# ver061_SignalAnalog.net
KiCad netlist of a schematic drawn in Altium Designer
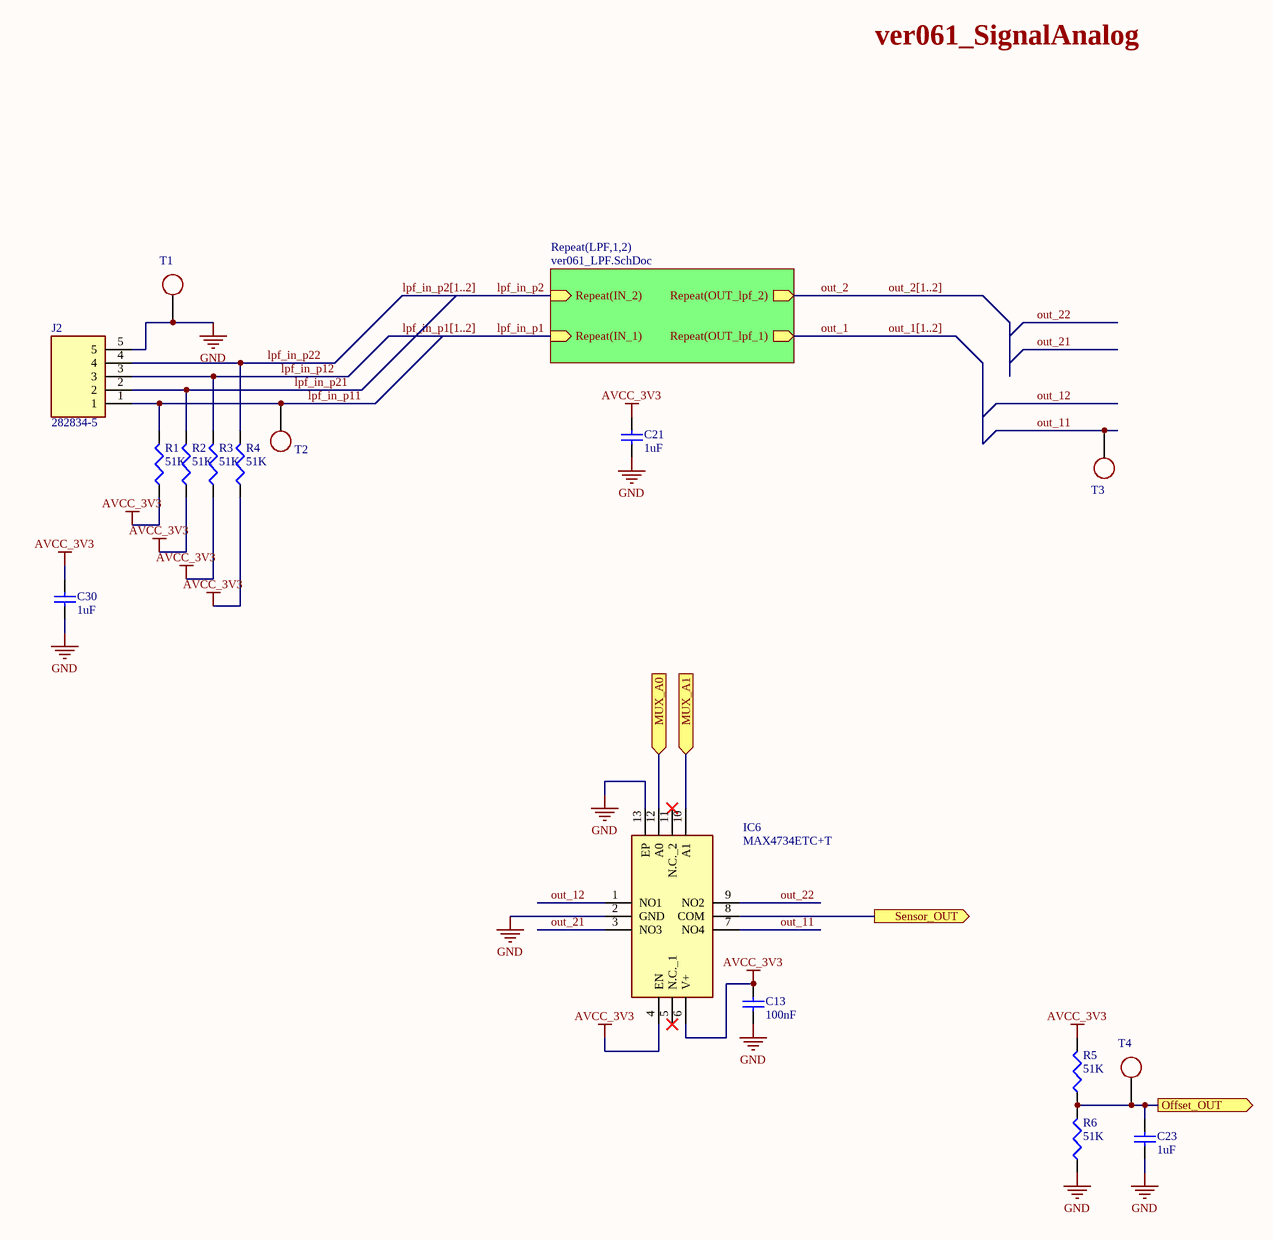
[diagram p0: ver061_SignalAnalog.SchDoc]

(export (version "E")
  (design (tool "Eeschema 10.0.6"))
  (components
    (comp (ref "C13")
      (value "100nF")
      (footprint "1608[0603]")
      (description "Capacitor (Semiconductor SIM Model)")
      (fields (field (name "Comment") "Cap Semi") (field (name "PUBLISHER") "Altium Limited"))
      (libsource (lib "Miscellaneous Devices") (part "Cap Semi"))
    )
    (comp (ref "C21")
      (value "1uF")
      (footprint "1608[0603]")
      (description "Capacitor (Semiconductor SIM Model)")
      (fields (field (name "Comment") "Cap Semi") (field (name "PUBLISHER") "Altium Limited"))
      (libsource (lib "Miscellaneous Devices") (part "Cap Semi"))
    )
    (comp (ref "C23")
      (value "1uF")
      (footprint "0402")
      (description "Capacitor (Semiconductor SIM Model)")
      (fields (field (name "Comment") "Cap Semi") (field (name "PUBLISHER") "Altium Limited"))
      (libsource (lib "Miscellaneous Devices") (part "Cap Semi"))
    )
    (comp (ref "C30")
      (value "1uF")
      (footprint "1608[0603]")
      (description "Capacitor (Semiconductor SIM Model)")
      (fields (field (name "Comment") "Cap Semi") (field (name "PUBLISHER") "Altium Limited"))
      (libsource (lib "Miscellaneous Devices") (part "Cap Semi"))
    )
    (comp (ref "IC6")
      (value "MAX4734ETC+T")
      (footprint "QFN50P300X300X80-13N")
      (description "Integrated Circuit")
      (fields (field (name "MOUSER PART NUMBER") "700-MAX4734ETCT"))
      (libsource (lib "*") (part "MAX4734ETC+T"))
    )
    (comp (ref "J2")
      (value "282834-5")
      (footprint "nanowire:2828345")
      (description "Connector")
      (fields (field (name "MOUSER PART NUMBER") "571-282834-5"))
      (libsource (lib "*") (part "282834-5"))
    )
    (comp (ref "R1")
      (value "51K")
      (footprint "RESC1608X55N")
      (description "Resistor")
      (fields (field (name "Comment") "Res3") (field (name "PUBLISHER") "Altium Limited"))
      (libsource (lib "Miscellaneous Devices") (part "Res3"))
    )
    (comp (ref "R2")
      (value "51K")
      (footprint "RESC1608X55N")
      (description "Resistor")
      (fields (field (name "Comment") "Res3") (field (name "PUBLISHER") "Altium Limited"))
      (libsource (lib "Miscellaneous Devices") (part "Res3"))
    )
    (comp (ref "R3")
      (value "51K")
      (footprint "RESC1608X55N")
      (description "Resistor")
      (fields (field (name "Comment") "Res3") (field (name "PUBLISHER") "Altium Limited"))
      (libsource (lib "Miscellaneous Devices") (part "Res3"))
    )
    (comp (ref "R4")
      (value "51K")
      (footprint "RESC1608X55N")
      (description "Resistor")
      (fields (field (name "Comment") "Res3") (field (name "PUBLISHER") "Altium Limited"))
      (libsource (lib "Miscellaneous Devices") (part "Res3"))
    )
    (comp (ref "R5")
      (value "51K")
      (footprint "RESC1005X35N")
      (description "Resistor")
      (fields (field (name "Comment") "Res3") (field (name "PUBLISHER") "Altium Limited"))
      (libsource (lib "Miscellaneous Devices") (part "Res3"))
    )
    (comp (ref "R6")
      (value "51K")
      (footprint "RESC1005X35N")
      (description "Resistor")
      (fields (field (name "Comment") "Res3") (field (name "PUBLISHER") "Altium Limited"))
      (libsource (lib "Miscellaneous Devices") (part "Res3"))
    )
    (comp (ref "T1")
      (value "TP_SMT")
      (footprint "TP_SMT_Round_0.6x0.6")
      (libsource (lib "nanowire") (part "TP_SMT"))
    )
    (comp (ref "T2")
      (value "TP_SMT")
      (footprint "TP_SMT_Round_0.6x0.6")
      (libsource (lib "nanowire") (part "TP_SMT"))
    )
    (comp (ref "T3")
      (value "TP_SMT")
      (footprint "TP_SMT_Round_0.6x0.6")
      (libsource (lib "nanowire") (part "TP_SMT"))
    )
    (comp (ref "T4")
      (value "TP_SMT")
      (footprint "TP_SMT_Round_0.6x0.6")
      (libsource (lib "nanowire") (part "TP_SMT"))
    )
  )
  (nets
    (net (code "1") (name "/MUX_A0") (class "Default")
      (node (ref "IC6") (pin "12") (pinfunction "A0_12") (pintype "passive"))
    )
    (net (code "2") (name "/MUX_A1") (class "Default")
      (node (ref "IC6") (pin "10") (pinfunction "A1_10") (pintype "passive"))
    )
    (net (code "3") (name "/Offset_OUT") (class "Default")
      (node (ref "C23") (pin "2") (pinfunction "2_2") (pintype "passive"))
      (node (ref "R5") (pin "1") (pinfunction "1_1") (pintype "passive"))
      (node (ref "R6") (pin "2") (pinfunction "2_2") (pintype "passive"))
      (node (ref "T4") (pin "1") (pinfunction "1_1") (pintype "passive"))
    )
    (net (code "4") (name "/Sensor_OUT") (class "Default")
      (node (ref "IC6") (pin "8") (pinfunction "COM_8") (pintype "passive"))
    )
    (net (code "9") (name "/lpf_in_p11") (class "Default")
      (node (ref "J2") (pin "1") (pinfunction "1_1") (pintype "passive"))
      (node (ref "R1") (pin "2") (pinfunction "2_2") (pintype "passive"))
      (node (ref "T2") (pin "1") (pinfunction "1_1") (pintype "passive"))
    )
    (net (code "10") (name "/lpf_in_p12") (class "Default")
      (node (ref "J2") (pin "3") (pinfunction "3_3") (pintype "passive"))
      (node (ref "R3") (pin "2") (pinfunction "2_2") (pintype "passive"))
    )
    (net (code "11") (name "/lpf_in_p21") (class "Default")
      (node (ref "J2") (pin "2") (pinfunction "2_2") (pintype "passive"))
      (node (ref "R2") (pin "2") (pinfunction "2_2") (pintype "passive"))
    )
    (net (code "12") (name "/lpf_in_p22") (class "Default")
      (node (ref "J2") (pin "4") (pinfunction "4_4") (pintype "passive"))
      (node (ref "R4") (pin "2") (pinfunction "2_2") (pintype "passive"))
    )
    (net (code "17") (name "/out_11") (class "Default")
      (node (ref "IC6") (pin "7") (pinfunction "NO4_7") (pintype "passive"))
      (node (ref "T3") (pin "1") (pinfunction "1_1") (pintype "passive"))
    )
    (net (code "18") (name "/out_12") (class "Default")
      (node (ref "IC6") (pin "1") (pinfunction "NO1_1") (pintype "passive"))
    )
    (net (code "19") (name "/out_21") (class "Default")
      (node (ref "IC6") (pin "3") (pinfunction "NO3_3") (pintype "passive"))
    )
    (net (code "20") (name "/out_22") (class "Default")
      (node (ref "IC6") (pin "9") (pinfunction "NO2_9") (pintype "passive"))
    )
    (net (code "21") (name "AVCC_3V3") (class "Default")
      (node (ref "C13") (pin "2") (pinfunction "2_2") (pintype "passive"))
      (node (ref "C21") (pin "2") (pinfunction "2_2") (pintype "passive"))
      (node (ref "C30") (pin "2") (pinfunction "2_2") (pintype "passive"))
      (node (ref "IC6") (pin "4") (pinfunction "EN_4") (pintype "passive"))
      (node (ref "IC6") (pin "6") (pinfunction "V+_6") (pintype "passive"))
      (node (ref "R1") (pin "1") (pinfunction "1_1") (pintype "passive"))
      (node (ref "R2") (pin "1") (pinfunction "1_1") (pintype "passive"))
      (node (ref "R3") (pin "1") (pinfunction "1_1") (pintype "passive"))
      (node (ref "R4") (pin "1") (pinfunction "1_1") (pintype "passive"))
      (node (ref "R5") (pin "2") (pinfunction "2_2") (pintype "passive"))
    )
    (net (code "22") (name "GND") (class "Default")
      (node (ref "C13") (pin "1") (pinfunction "1_1") (pintype "passive"))
      (node (ref "C21") (pin "1") (pinfunction "1_1") (pintype "passive"))
      (node (ref "C23") (pin "1") (pinfunction "1_1") (pintype "passive"))
      (node (ref "C30") (pin "1") (pinfunction "1_1") (pintype "passive"))
      (node (ref "IC6") (pin "13") (pinfunction "EP_13") (pintype "passive"))
      (node (ref "IC6") (pin "2") (pinfunction "GND_2") (pintype "passive"))
      (node (ref "J2") (pin "5") (pinfunction "5_5") (pintype "passive"))
      (node (ref "R6") (pin "1") (pinfunction "1_1") (pintype "passive"))
      (node (ref "T1") (pin "1") (pinfunction "1_1") (pintype "passive"))
    )
    (net (code "23") (name "unconnected-(IC6-N.C._1-Pad5)") (class "Default")
      (node (ref "IC6") (pin "5") (pinfunction "N.C._1_5") (pintype "passive+no_connect"))
    )
    (net (code "24") (name "unconnected-(IC6-N.C._2-Pad11)") (class "Default")
      (node (ref "IC6") (pin "11") (pinfunction "N.C._2_11") (pintype "passive+no_connect"))
    )
  )
)
